# prim_analog_in.net
KiCad netlist of a schematic drawn in Altium Designer
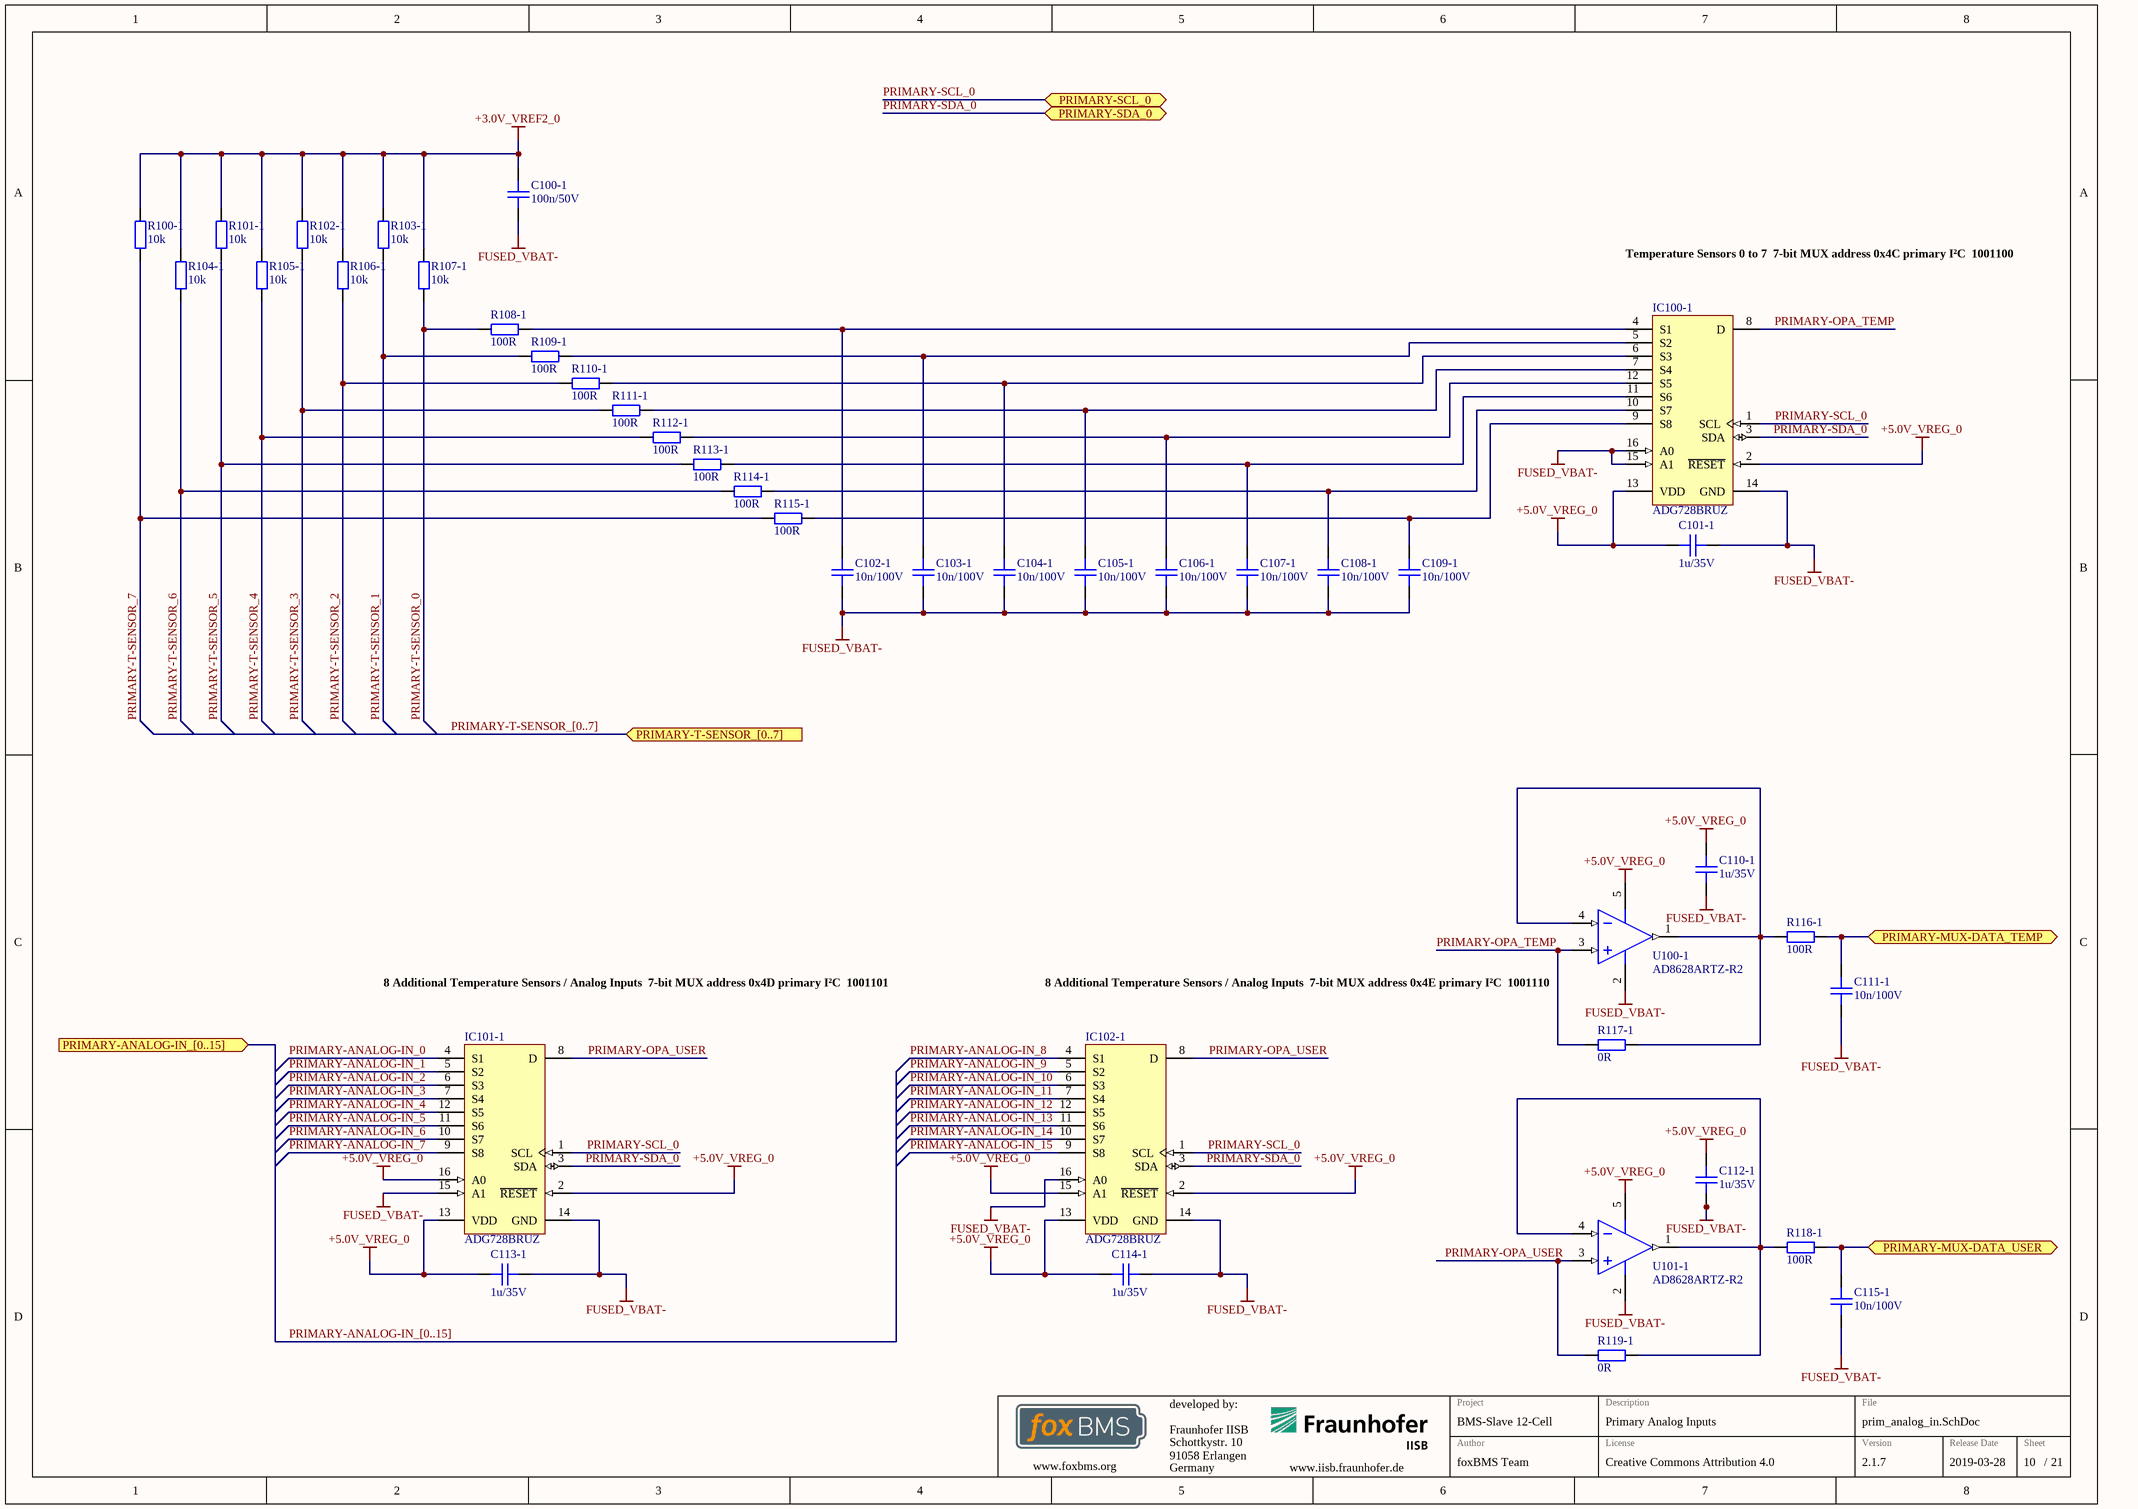
[diagram p0: prim_analog_in.SchDoc]

(export (version "E")
  (design (tool "Eeschema 10.0.6"))
  (components
    (comp (ref "C100-1")
      (value "100n/50V")
      (footprint "CAPC1608X08N")
      (description "MLCC")
      (fields (field (name "PART NUMBER") "gen_C_ceramic_100n_50V_X7R_0603"))
      (libsource (lib "OE750") (part "C"))
    )
    (comp (ref "C101-1")
      (value "1u/35V")
      (footprint "CAPC1608X08N")
      (description "MLCC")
      (fields (field (name "PART NUMBER") "gen_C_ceramic_1u_35V_X7R_0603"))
      (libsource (lib "OE750") (part "C"))
    )
    (comp (ref "C102-1")
      (value "10n/100V")
      (footprint "CAPC1608X08N")
      (description "MLCC")
      (fields (field (name "PART NUMBER") "gen_C_ceramic_10n_100V_X7R_0603"))
      (libsource (lib "OE750") (part "C"))
    )
    (comp (ref "C103-1")
      (value "10n/100V")
      (footprint "CAPC1608X08N")
      (description "MLCC")
      (fields (field (name "PART NUMBER") "gen_C_ceramic_10n_100V_X7R_0603"))
      (libsource (lib "OE750") (part "C"))
    )
    (comp (ref "C104-1")
      (value "10n/100V")
      (footprint "CAPC1608X08N")
      (description "MLCC")
      (fields (field (name "PART NUMBER") "gen_C_ceramic_10n_100V_X7R_0603"))
      (libsource (lib "OE750") (part "C"))
    )
    (comp (ref "C105-1")
      (value "10n/100V")
      (footprint "CAPC1608X08N")
      (description "MLCC")
      (fields (field (name "PART NUMBER") "gen_C_ceramic_10n_100V_X7R_0603"))
      (libsource (lib "OE750") (part "C"))
    )
    (comp (ref "C106-1")
      (value "10n/100V")
      (footprint "CAPC1608X08N")
      (description "MLCC")
      (fields (field (name "PART NUMBER") "gen_C_ceramic_10n_100V_X7R_0603"))
      (libsource (lib "OE750") (part "C"))
    )
    (comp (ref "C107-1")
      (value "10n/100V")
      (footprint "CAPC1608X08N")
      (description "MLCC")
      (fields (field (name "PART NUMBER") "gen_C_ceramic_10n_100V_X7R_0603"))
      (libsource (lib "OE750") (part "C"))
    )
    (comp (ref "C108-1")
      (value "10n/100V")
      (footprint "CAPC1608X08N")
      (description "MLCC")
      (fields (field (name "PART NUMBER") "gen_C_ceramic_10n_100V_X7R_0603"))
      (libsource (lib "OE750") (part "C"))
    )
    (comp (ref "C109-1")
      (value "10n/100V")
      (footprint "CAPC1608X08N")
      (description "MLCC")
      (fields (field (name "PART NUMBER") "gen_C_ceramic_10n_100V_X7R_0603"))
      (libsource (lib "OE750") (part "C"))
    )
    (comp (ref "C110-1")
      (value "1u/35V")
      (footprint "CAPC1608X08N")
      (description "MLCC")
      (fields (field (name "PART NUMBER") "gen_C_ceramic_1u_35V_X7R_0603"))
      (libsource (lib "OE750") (part "C"))
    )
    (comp (ref "C111-1")
      (value "10n/100V")
      (footprint "CAPC1608X08N")
      (description "MLCC")
      (fields (field (name "PART NUMBER") "gen_C_ceramic_10n_100V_X7R_0603"))
      (libsource (lib "OE750") (part "C"))
    )
    (comp (ref "C112-1")
      (value "1u/35V")
      (footprint "CAPC1608X08N")
      (description "MLCC")
      (fields (field (name "PART NUMBER") "gen_C_ceramic_1u_35V_X7R_0603"))
      (libsource (lib "OE750") (part "C"))
    )
    (comp (ref "C113-1")
      (value "1u/35V")
      (footprint "CAPC1608X08N")
      (description "MLCC")
      (fields (field (name "PART NUMBER") "gen_C_ceramic_1u_35V_X7R_0603"))
      (libsource (lib "OE750") (part "C"))
    )
    (comp (ref "C114-1")
      (value "1u/35V")
      (footprint "CAPC1608X08N")
      (description "MLCC")
      (fields (field (name "PART NUMBER") "gen_C_ceramic_1u_35V_X7R_0603"))
      (libsource (lib "OE750") (part "C"))
    )
    (comp (ref "C115-1")
      (value "10n/100V")
      (footprint "CAPC1608X08N")
      (description "MLCC")
      (fields (field (name "PART NUMBER") "gen_C_ceramic_10n_100V_X7R_0603"))
      (libsource (lib "OE750") (part "C"))
    )
    (comp (ref "IC100-1")
      (value "ADG728BRUZ")
      (footprint "ADI-RU-16_M")
      (fields (field (name "MANUFACTURER") "Analog Devices"))
      (libsource (lib "Altium Content Vault") (part "ADI-ADG728-RU-16"))
    )
    (comp (ref "IC101-1")
      (value "ADG728BRUZ")
      (footprint "ADI-RU-16_M")
      (fields (field (name "MANUFACTURER") "Analog Devices"))
      (libsource (lib "Altium Content Vault") (part "ADI-ADG728-RU-16"))
    )
    (comp (ref "IC102-1")
      (value "ADG728BRUZ")
      (footprint "ADI-RU-16_M")
      (fields (field (name "MANUFACTURER") "Analog Devices"))
      (libsource (lib "Altium Content Vault") (part "ADI-ADG728-RU-16"))
    )
    (comp (ref "R100-1")
      (value "10k")
      (footprint "RESC1608X05N")
      (description "SMD Resistor 10k 0603")
      (fields (field (name "PART NUMBER") "gen_R_10k_0603") (field (name "TOLERANCE") "1%"))
      (libsource (lib "OE750") (part "R"))
    )
    (comp (ref "R101-1")
      (value "10k")
      (footprint "RESC1608X05N")
      (description "SMD Resistor 10k 0603")
      (fields (field (name "PART NUMBER") "gen_R_10k_0603") (field (name "TOLERANCE") "1%"))
      (libsource (lib "OE750") (part "R"))
    )
    (comp (ref "R102-1")
      (value "10k")
      (footprint "RESC1608X05N")
      (description "SMD Resistor 10k 0603")
      (fields (field (name "PART NUMBER") "gen_R_10k_0603") (field (name "TOLERANCE") "1%"))
      (libsource (lib "OE750") (part "R"))
    )
    (comp (ref "R103-1")
      (value "10k")
      (footprint "RESC1608X05N")
      (description "SMD Resistor 10k 0603")
      (fields (field (name "PART NUMBER") "gen_R_10k_0603") (field (name "TOLERANCE") "1%"))
      (libsource (lib "OE750") (part "R"))
    )
    (comp (ref "R104-1")
      (value "10k")
      (footprint "RESC1608X05N")
      (description "SMD Resistor 10k 0603")
      (fields (field (name "PART NUMBER") "gen_R_10k_0603") (field (name "TOLERANCE") "1%"))
      (libsource (lib "OE750") (part "R"))
    )
    (comp (ref "R105-1")
      (value "10k")
      (footprint "RESC1608X05N")
      (description "SMD Resistor 10k 0603")
      (fields (field (name "PART NUMBER") "gen_R_10k_0603") (field (name "TOLERANCE") "1%"))
      (libsource (lib "OE750") (part "R"))
    )
    (comp (ref "R106-1")
      (value "10k")
      (footprint "RESC1608X05N")
      (description "SMD Resistor 10k 0603")
      (fields (field (name "PART NUMBER") "gen_R_10k_0603") (field (name "TOLERANCE") "1%"))
      (libsource (lib "OE750") (part "R"))
    )
    (comp (ref "R107-1")
      (value "10k")
      (footprint "RESC1608X05N")
      (description "SMD Resistor 10k 0603")
      (fields (field (name "PART NUMBER") "gen_R_10k_0603") (field (name "TOLERANCE") "1%"))
      (libsource (lib "OE750") (part "R"))
    )
    (comp (ref "R108-1")
      (value "100R")
      (footprint "RESC1608X05N")
      (description "SMD Resistor 100R 0603")
      (fields (field (name "PART NUMBER") "gen_R_100R_0603") (field (name "TOLERANCE") "1%"))
      (libsource (lib "OE750") (part "R"))
    )
    (comp (ref "R109-1")
      (value "100R")
      (footprint "RESC1608X05N")
      (description "SMD Resistor 100R 0603")
      (fields (field (name "PART NUMBER") "gen_R_100R_0603") (field (name "TOLERANCE") "1%"))
      (libsource (lib "OE750") (part "R"))
    )
    (comp (ref "R110-1")
      (value "100R")
      (footprint "RESC1608X05N")
      (description "SMD Resistor 100R 0603")
      (fields (field (name "PART NUMBER") "gen_R_100R_0603") (field (name "TOLERANCE") "1%"))
      (libsource (lib "OE750") (part "R"))
    )
    (comp (ref "R111-1")
      (value "100R")
      (footprint "RESC1608X05N")
      (description "SMD Resistor 100R 0603")
      (fields (field (name "PART NUMBER") "gen_R_100R_0603") (field (name "TOLERANCE") "1%"))
      (libsource (lib "OE750") (part "R"))
    )
    (comp (ref "R112-1")
      (value "100R")
      (footprint "RESC1608X05N")
      (description "SMD Resistor 100R 0603")
      (fields (field (name "PART NUMBER") "gen_R_100R_0603") (field (name "TOLERANCE") "1%"))
      (libsource (lib "OE750") (part "R"))
    )
    (comp (ref "R113-1")
      (value "100R")
      (footprint "RESC1608X05N")
      (description "SMD Resistor 100R 0603")
      (fields (field (name "PART NUMBER") "gen_R_100R_0603") (field (name "TOLERANCE") "1%"))
      (libsource (lib "OE750") (part "R"))
    )
    (comp (ref "R114-1")
      (value "100R")
      (footprint "RESC1608X05N")
      (description "SMD Resistor 100R 0603")
      (fields (field (name "PART NUMBER") "gen_R_100R_0603") (field (name "TOLERANCE") "1%"))
      (libsource (lib "OE750") (part "R"))
    )
    (comp (ref "R115-1")
      (value "100R")
      (footprint "RESC1608X05N")
      (description "SMD Resistor 100R 0603")
      (fields (field (name "PART NUMBER") "gen_R_100R_0603") (field (name "TOLERANCE") "1%"))
      (libsource (lib "OE750") (part "R"))
    )
    (comp (ref "R116-1")
      (value "100R")
      (footprint "RESC1608X05N")
      (description "SMD Resistor 100R 0603")
      (fields (field (name "PART NUMBER") "gen_R_100R_0603") (field (name "TOLERANCE") "1%"))
      (libsource (lib "OE750") (part "R"))
    )
    (comp (ref "R117-1")
      (value "0R")
      (footprint "RESC1608X05N")
      (description "SMD Resistor 0R 0603")
      (fields (field (name "PART NUMBER") "gen_R_0R_0603") (field (name "POWER") "0.1W"))
      (libsource (lib "OE750") (part "R"))
    )
    (comp (ref "R118-1")
      (value "100R")
      (footprint "RESC1608X05N")
      (description "SMD Resistor 100R 0603")
      (fields (field (name "PART NUMBER") "gen_R_100R_0603") (field (name "TOLERANCE") "1%"))
      (libsource (lib "OE750") (part "R"))
    )
    (comp (ref "R119-1")
      (value "0R")
      (footprint "RESC1608X05N")
      (description "SMD Resistor 0R 0603")
      (fields (field (name "PART NUMBER") "gen_R_0R_0603") (field (name "POWER") "0.1W"))
      (libsource (lib "OE750") (part "R"))
    )
    (comp (ref "U100-1")
      (value "AD8628ARTZ-R2")
      (footprint "ADI-RJ-5_M")
      (fields (field (name "MANUFACTURER") "Analog Devices") (field (name "GENERIC PART NUMBER") "AD8628"))
      (libsource (lib "Altium Content Vault") (part "ADI-ADxxxx-X-5"))
    )
    (comp (ref "U101-1")
      (value "AD8628ARTZ-R2")
      (footprint "ADI-RJ-5_M")
      (fields (field (name "MANUFACTURER") "Analog Devices") (field (name "GENERIC PART NUMBER") "AD8628"))
      (libsource (lib "Altium Content Vault") (part "ADI-ADxxxx-X-5"))
    )
  )
  (nets
    (net (code "1") (name "+3.0V_VREF2_0") (class "Default")
      (node (ref "C100-1") (pin "2") (pinfunction "2_2") (pintype "passive"))
      (node (ref "R100-1") (pin "2") (pinfunction "2_2") (pintype "passive"))
      (node (ref "R101-1") (pin "2") (pinfunction "2_2") (pintype "passive"))
      (node (ref "R102-1") (pin "2") (pinfunction "2_2") (pintype "passive"))
      (node (ref "R103-1") (pin "2") (pinfunction "2_2") (pintype "passive"))
      (node (ref "R104-1") (pin "2") (pinfunction "2_2") (pintype "passive"))
      (node (ref "R105-1") (pin "2") (pinfunction "2_2") (pintype "passive"))
      (node (ref "R106-1") (pin "2") (pinfunction "2_2") (pintype "passive"))
      (node (ref "R107-1") (pin "2") (pinfunction "2_2") (pintype "passive"))
    )
    (net (code "2") (name "+5.0V_VREG_0") (class "Default")
      (node (ref "C101-1") (pin "2") (pinfunction "2_2") (pintype "passive"))
      (node (ref "C110-1") (pin "2") (pinfunction "2_2") (pintype "passive"))
      (node (ref "C112-1") (pin "2") (pinfunction "2_2") (pintype "passive"))
      (node (ref "C113-1") (pin "2") (pinfunction "2_2") (pintype "passive"))
      (node (ref "C114-1") (pin "2") (pinfunction "2_2") (pintype "passive"))
      (node (ref "IC100-1") (pin "13") (pinfunction "VDD_13") (pintype "power_in"))
      (node (ref "IC100-1") (pin "2") (pinfunction "~{RESET}_2") (pintype "input"))
      (node (ref "IC101-1") (pin "13") (pinfunction "VDD_13") (pintype "power_in"))
      (node (ref "IC101-1") (pin "16") (pinfunction "A0_16") (pintype "input"))
      (node (ref "IC101-1") (pin "2") (pinfunction "~{RESET}_2") (pintype "input"))
      (node (ref "IC102-1") (pin "13") (pinfunction "VDD_13") (pintype "power_in"))
      (node (ref "IC102-1") (pin "15") (pinfunction "A1_15") (pintype "input"))
      (node (ref "IC102-1") (pin "2") (pinfunction "~{RESET}_2") (pintype "input"))
      (node (ref "U100-1") (pin "5") (pinfunction "+V_5") (pintype "power_in"))
      (node (ref "U101-1") (pin "5") (pinfunction "+V_5") (pintype "power_in"))
    )
    (net (code "3") (name "/PRIMARY-ANALOG-IN_0") (class "Default")
      (node (ref "IC101-1") (pin "4") (pinfunction "S1_4") (pintype "passive"))
    )
    (net (code "4") (name "/PRIMARY-ANALOG-IN_1") (class "Default")
      (node (ref "IC101-1") (pin "5") (pinfunction "S2_5") (pintype "passive"))
    )
    (net (code "5") (name "/PRIMARY-ANALOG-IN_2") (class "Default")
      (node (ref "IC101-1") (pin "6") (pinfunction "S3_6") (pintype "passive"))
    )
    (net (code "6") (name "/PRIMARY-ANALOG-IN_3") (class "Default")
      (node (ref "IC101-1") (pin "7") (pinfunction "S4_7") (pintype "passive"))
    )
    (net (code "7") (name "/PRIMARY-ANALOG-IN_4") (class "Default")
      (node (ref "IC101-1") (pin "12") (pinfunction "S5_12") (pintype "passive"))
    )
    (net (code "8") (name "/PRIMARY-ANALOG-IN_5") (class "Default")
      (node (ref "IC101-1") (pin "11") (pinfunction "S6_11") (pintype "passive"))
    )
    (net (code "9") (name "/PRIMARY-ANALOG-IN_6") (class "Default")
      (node (ref "IC101-1") (pin "10") (pinfunction "S7_10") (pintype "passive"))
    )
    (net (code "10") (name "/PRIMARY-ANALOG-IN_7") (class "Default")
      (node (ref "IC101-1") (pin "9") (pinfunction "S8_9") (pintype "passive"))
    )
    (net (code "11") (name "/PRIMARY-ANALOG-IN_8") (class "Default")
      (node (ref "IC102-1") (pin "4") (pinfunction "S1_4") (pintype "passive"))
    )
    (net (code "12") (name "/PRIMARY-ANALOG-IN_9") (class "Default")
      (node (ref "IC102-1") (pin "5") (pinfunction "S2_5") (pintype "passive"))
    )
    (net (code "13") (name "/PRIMARY-ANALOG-IN_10") (class "Default")
      (node (ref "IC102-1") (pin "6") (pinfunction "S3_6") (pintype "passive"))
    )
    (net (code "14") (name "/PRIMARY-ANALOG-IN_11") (class "Default")
      (node (ref "IC102-1") (pin "7") (pinfunction "S4_7") (pintype "passive"))
    )
    (net (code "15") (name "/PRIMARY-ANALOG-IN_12") (class "Default")
      (node (ref "IC102-1") (pin "12") (pinfunction "S5_12") (pintype "passive"))
    )
    (net (code "16") (name "/PRIMARY-ANALOG-IN_13") (class "Default")
      (node (ref "IC102-1") (pin "11") (pinfunction "S6_11") (pintype "passive"))
    )
    (net (code "17") (name "/PRIMARY-ANALOG-IN_14") (class "Default")
      (node (ref "IC102-1") (pin "10") (pinfunction "S7_10") (pintype "passive"))
    )
    (net (code "18") (name "/PRIMARY-ANALOG-IN_15") (class "Default")
      (node (ref "IC102-1") (pin "9") (pinfunction "S8_9") (pintype "passive"))
    )
    (net (code "20") (name "/PRIMARY-MUX-DATA_TEMP") (class "Default")
      (node (ref "C111-1") (pin "2") (pinfunction "2_2") (pintype "passive"))
      (node (ref "R116-1") (pin "2") (pinfunction "2_2") (pintype "passive"))
    )
    (net (code "21") (name "/PRIMARY-MUX-DATA_USER") (class "Default")
      (node (ref "C115-1") (pin "2") (pinfunction "2_2") (pintype "passive"))
      (node (ref "R118-1") (pin "2") (pinfunction "2_2") (pintype "passive"))
    )
    (net (code "22") (name "/PRIMARY-OPA_TEMP") (class "Default")
      (node (ref "IC100-1") (pin "8") (pinfunction "D_8") (pintype "passive"))
      (node (ref "R117-1") (pin "1") (pinfunction "1_1") (pintype "passive"))
      (node (ref "U100-1") (pin "3") (pinfunction "+IN_3") (pintype "input"))
    )
    (net (code "23") (name "/PRIMARY-OPA_USER") (class "Default")
      (node (ref "IC101-1") (pin "8") (pinfunction "D_8") (pintype "passive"))
      (node (ref "IC102-1") (pin "8") (pinfunction "D_8") (pintype "passive"))
      (node (ref "R119-1") (pin "1") (pinfunction "1_1") (pintype "passive"))
      (node (ref "U101-1") (pin "3") (pinfunction "+IN_3") (pintype "input"))
    )
    (net (code "24") (name "/PRIMARY-SCL_0") (class "Default")
      (node (ref "IC100-1") (pin "1") (pinfunction "SCL_1") (pintype "input"))
      (node (ref "IC101-1") (pin "1") (pinfunction "SCL_1") (pintype "input"))
      (node (ref "IC102-1") (pin "1") (pinfunction "SCL_1") (pintype "input"))
    )
    (net (code "25") (name "/PRIMARY-SDA_0") (class "Default")
      (node (ref "IC100-1") (pin "3") (pinfunction "SDA_3") (pintype "bidirectional"))
      (node (ref "IC101-1") (pin "3") (pinfunction "SDA_3") (pintype "bidirectional"))
      (node (ref "IC102-1") (pin "3") (pinfunction "SDA_3") (pintype "bidirectional"))
    )
    (net (code "26") (name "/PRIMARY-T-SENSOR_0") (class "Default")
      (node (ref "R107-1") (pin "1") (pinfunction "1_1") (pintype "passive"))
      (node (ref "R108-1") (pin "2") (pinfunction "2_2") (pintype "passive"))
    )
    (net (code "27") (name "/PRIMARY-T-SENSOR_1") (class "Default")
      (node (ref "R103-1") (pin "1") (pinfunction "1_1") (pintype "passive"))
      (node (ref "R109-1") (pin "2") (pinfunction "2_2") (pintype "passive"))
    )
    (net (code "28") (name "/PRIMARY-T-SENSOR_2") (class "Default")
      (node (ref "R106-1") (pin "1") (pinfunction "1_1") (pintype "passive"))
      (node (ref "R110-1") (pin "2") (pinfunction "2_2") (pintype "passive"))
    )
    (net (code "29") (name "/PRIMARY-T-SENSOR_3") (class "Default")
      (node (ref "R102-1") (pin "1") (pinfunction "1_1") (pintype "passive"))
      (node (ref "R111-1") (pin "2") (pinfunction "2_2") (pintype "passive"))
    )
    (net (code "30") (name "/PRIMARY-T-SENSOR_4") (class "Default")
      (node (ref "R105-1") (pin "1") (pinfunction "1_1") (pintype "passive"))
      (node (ref "R112-1") (pin "2") (pinfunction "2_2") (pintype "passive"))
    )
    (net (code "31") (name "/PRIMARY-T-SENSOR_5") (class "Default")
      (node (ref "R101-1") (pin "1") (pinfunction "1_1") (pintype "passive"))
      (node (ref "R113-1") (pin "2") (pinfunction "2_2") (pintype "passive"))
    )
    (net (code "32") (name "/PRIMARY-T-SENSOR_6") (class "Default")
      (node (ref "R104-1") (pin "1") (pinfunction "1_1") (pintype "passive"))
      (node (ref "R114-1") (pin "2") (pinfunction "2_2") (pintype "passive"))
    )
    (net (code "33") (name "/PRIMARY-T-SENSOR_7") (class "Default")
      (node (ref "R100-1") (pin "1") (pinfunction "1_1") (pintype "passive"))
      (node (ref "R115-1") (pin "2") (pinfunction "2_2") (pintype "passive"))
    )
    (net (code "35") (name "FUSED_VBAT-") (class "Default")
      (node (ref "C100-1") (pin "1") (pinfunction "1_1") (pintype "passive"))
      (node (ref "C101-1") (pin "1") (pinfunction "1_1") (pintype "passive"))
      (node (ref "C102-1") (pin "1") (pinfunction "1_1") (pintype "passive"))
      (node (ref "C103-1") (pin "1") (pinfunction "1_1") (pintype "passive"))
      (node (ref "C104-1") (pin "1") (pinfunction "1_1") (pintype "passive"))
      (node (ref "C105-1") (pin "1") (pinfunction "1_1") (pintype "passive"))
      (node (ref "C106-1") (pin "1") (pinfunction "1_1") (pintype "passive"))
      (node (ref "C107-1") (pin "1") (pinfunction "1_1") (pintype "passive"))
      (node (ref "C108-1") (pin "1") (pinfunction "1_1") (pintype "passive"))
      (node (ref "C109-1") (pin "1") (pinfunction "1_1") (pintype "passive"))
      (node (ref "C110-1") (pin "1") (pinfunction "1_1") (pintype "passive"))
      (node (ref "C111-1") (pin "1") (pinfunction "1_1") (pintype "passive"))
      (node (ref "C112-1") (pin "1") (pinfunction "1_1") (pintype "passive"))
      (node (ref "C113-1") (pin "1") (pinfunction "1_1") (pintype "passive"))
      (node (ref "C114-1") (pin "1") (pinfunction "1_1") (pintype "passive"))
      (node (ref "C115-1") (pin "1") (pinfunction "1_1") (pintype "passive"))
      (node (ref "IC100-1") (pin "14") (pinfunction "GND_14") (pintype "power_in"))
      (node (ref "IC100-1") (pin "15") (pinfunction "A1_15") (pintype "input"))
      (node (ref "IC100-1") (pin "16") (pinfunction "A0_16") (pintype "input"))
      (node (ref "IC101-1") (pin "14") (pinfunction "GND_14") (pintype "power_in"))
      (node (ref "IC101-1") (pin "15") (pinfunction "A1_15") (pintype "input"))
      (node (ref "IC102-1") (pin "14") (pinfunction "GND_14") (pintype "power_in"))
      (node (ref "IC102-1") (pin "16") (pinfunction "A0_16") (pintype "input"))
      (node (ref "U100-1") (pin "2") (pinfunction "-V_2") (pintype "power_in"))
      (node (ref "U101-1") (pin "2") (pinfunction "-V_2") (pintype "power_in"))
    )
    (net (code "36") (name "Net-(IC100-1-S1)") (class "Default")
      (node (ref "C102-1") (pin "2") (pinfunction "2_2") (pintype "passive"))
      (node (ref "IC100-1") (pin "4") (pinfunction "S1_4") (pintype "passive"))
      (node (ref "R108-1") (pin "1") (pinfunction "1_1") (pintype "passive"))
    )
    (net (code "37") (name "Net-(IC100-1-S2)") (class "Default")
      (node (ref "C103-1") (pin "2") (pinfunction "2_2") (pintype "passive"))
      (node (ref "IC100-1") (pin "5") (pinfunction "S2_5") (pintype "passive"))
      (node (ref "R109-1") (pin "1") (pinfunction "1_1") (pintype "passive"))
    )
    (net (code "38") (name "Net-(IC100-1-S3)") (class "Default")
      (node (ref "C104-1") (pin "2") (pinfunction "2_2") (pintype "passive"))
      (node (ref "IC100-1") (pin "6") (pinfunction "S3_6") (pintype "passive"))
      (node (ref "R110-1") (pin "1") (pinfunction "1_1") (pintype "passive"))
    )
    (net (code "39") (name "Net-(IC100-1-S4)") (class "Default")
      (node (ref "C105-1") (pin "2") (pinfunction "2_2") (pintype "passive"))
      (node (ref "IC100-1") (pin "7") (pinfunction "S4_7") (pintype "passive"))
      (node (ref "R111-1") (pin "1") (pinfunction "1_1") (pintype "passive"))
    )
    (net (code "40") (name "Net-(IC100-1-S5)") (class "Default")
      (node (ref "C106-1") (pin "2") (pinfunction "2_2") (pintype "passive"))
      (node (ref "IC100-1") (pin "12") (pinfunction "S5_12") (pintype "passive"))
      (node (ref "R112-1") (pin "1") (pinfunction "1_1") (pintype "passive"))
    )
    (net (code "41") (name "Net-(IC100-1-S6)") (class "Default")
      (node (ref "C107-1") (pin "2") (pinfunction "2_2") (pintype "passive"))
      (node (ref "IC100-1") (pin "11") (pinfunction "S6_11") (pintype "passive"))
      (node (ref "R113-1") (pin "1") (pinfunction "1_1") (pintype "passive"))
    )
    (net (code "42") (name "Net-(IC100-1-S7)") (class "Default")
      (node (ref "C108-1") (pin "2") (pinfunction "2_2") (pintype "passive"))
      (node (ref "IC100-1") (pin "10") (pinfunction "S7_10") (pintype "passive"))
      (node (ref "R114-1") (pin "1") (pinfunction "1_1") (pintype "passive"))
    )
    (net (code "43") (name "Net-(IC100-1-S8)") (class "Default")
      (node (ref "C109-1") (pin "2") (pinfunction "2_2") (pintype "passive"))
      (node (ref "IC100-1") (pin "9") (pinfunction "S8_9") (pintype "passive"))
      (node (ref "R115-1") (pin "1") (pinfunction "1_1") (pintype "passive"))
    )
    (net (code "44") (name "Net-(U100-1--IN)") (class "Default")
      (node (ref "R116-1") (pin "1") (pinfunction "1_1") (pintype "passive"))
      (node (ref "R117-1") (pin "2") (pinfunction "2_2") (pintype "passive"))
      (node (ref "U100-1") (pin "1") (pinfunction "OUT_1") (pintype "output"))
      (node (ref "U100-1") (pin "4") (pinfunction "-IN_4") (pintype "input"))
    )
    (net (code "45") (name "Net-(U101-1--IN)") (class "Default")
      (node (ref "R118-1") (pin "1") (pinfunction "1_1") (pintype "passive"))
      (node (ref "R119-1") (pin "2") (pinfunction "2_2") (pintype "passive"))
      (node (ref "U101-1") (pin "1") (pinfunction "OUT_1") (pintype "output"))
      (node (ref "U101-1") (pin "4") (pinfunction "-IN_4") (pintype "input"))
    )
  )
)
